# or-stm32-ds.net
KiCad netlist of a schematic drawn in EAGLE
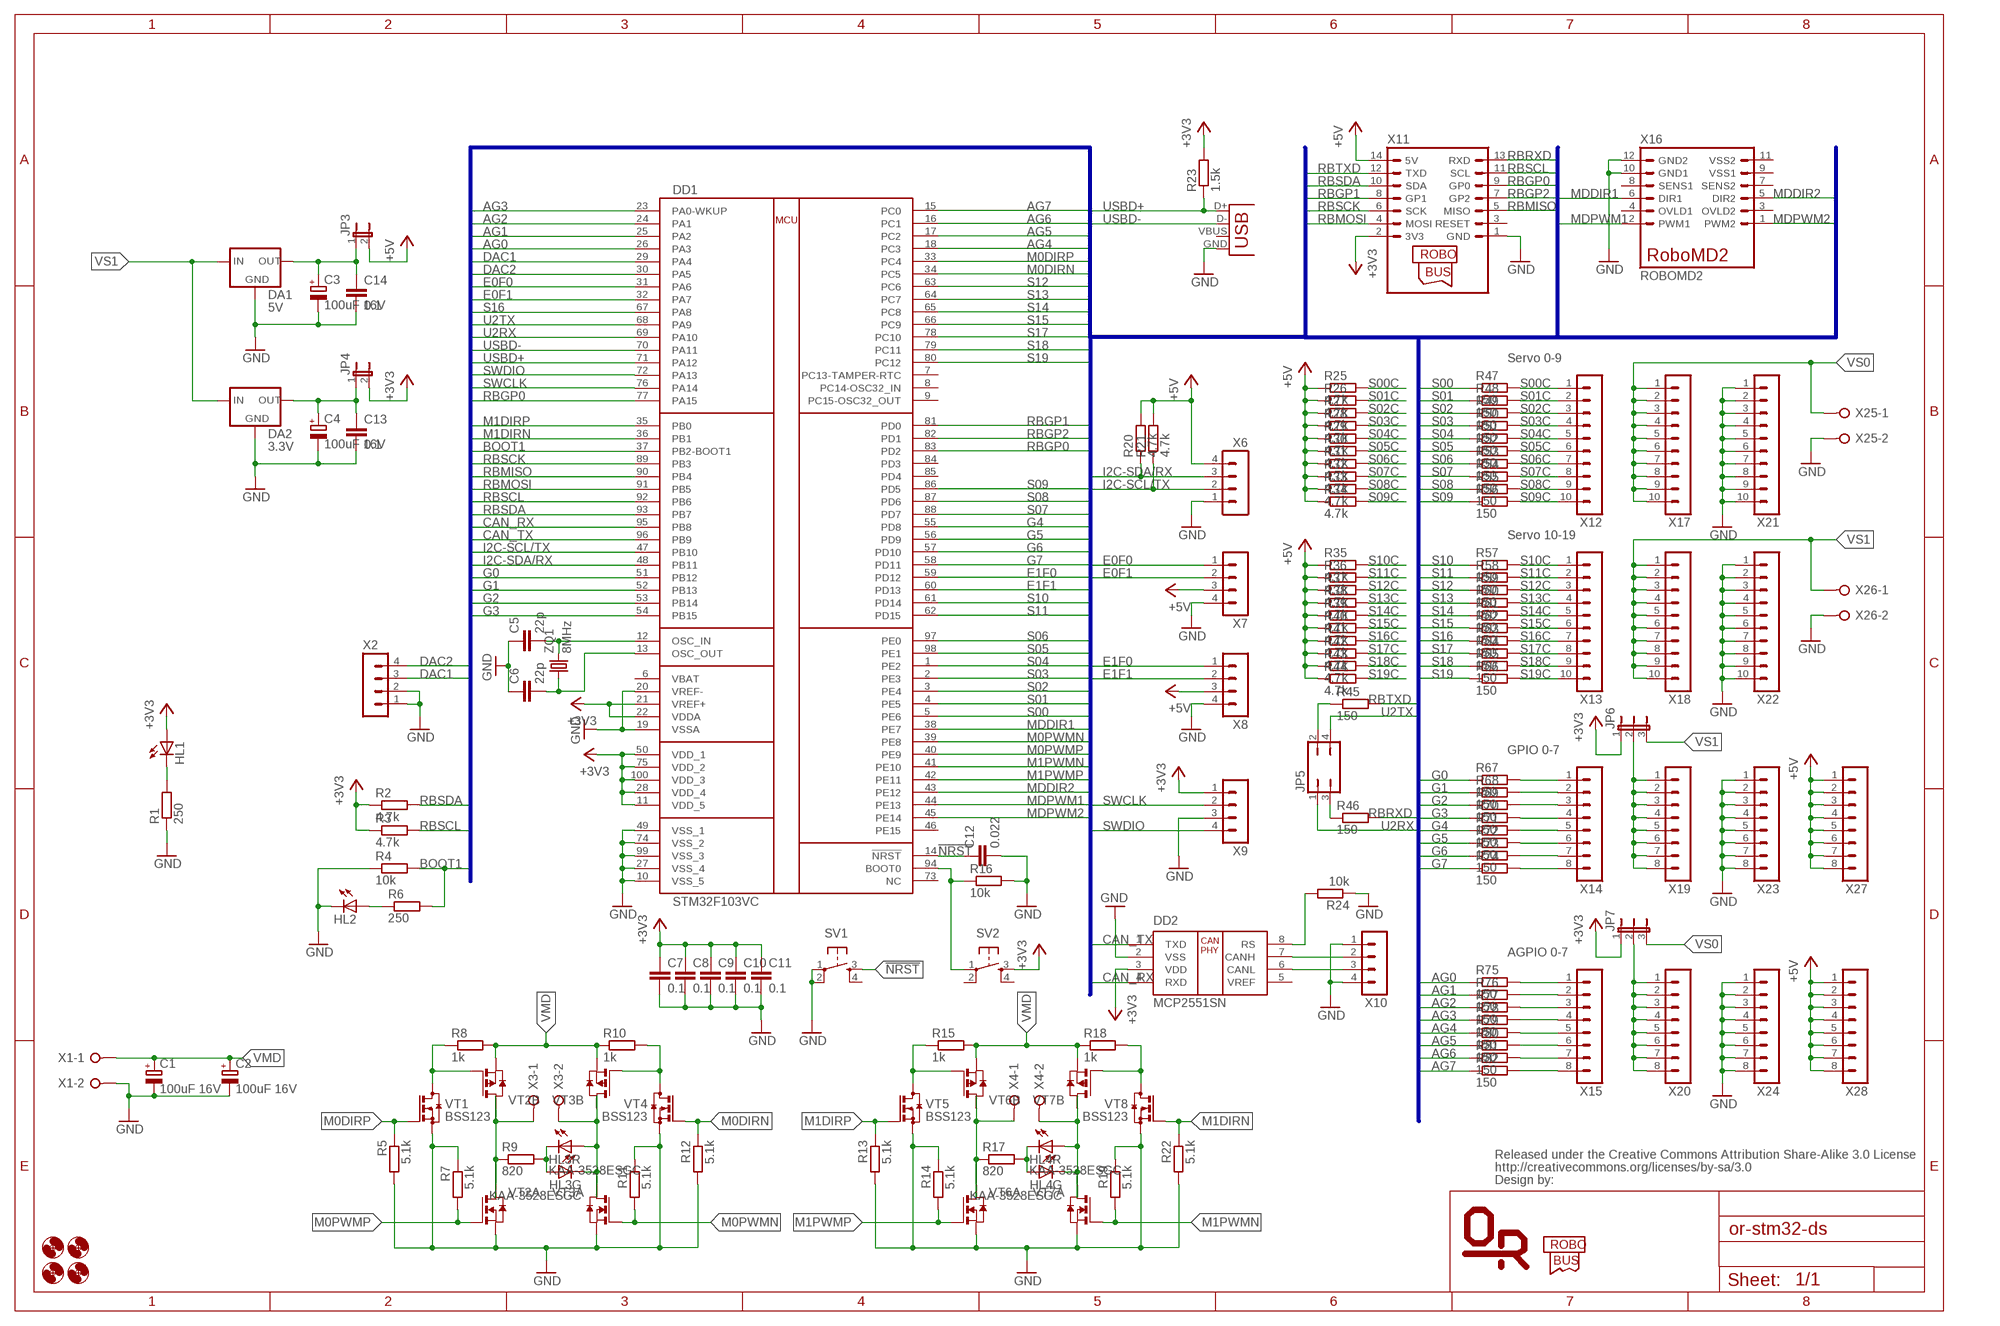
[diagram p0: schematic, sheet 1]

(export (version "E")
  (design (tool "Eeschema 10.0.6"))
  (components
    (comp (ref "C1")
      (value "100uF 16V")
      (footprint "eagle-import:E3,5-8")
      (libsource (lib "eagle-import") (part "CPOL-EUE3.5-8"))
    )
    (comp (ref "C2")
      (value "100uF 16V")
      (footprint "eagle-import:E3,5-8")
      (libsource (lib "eagle-import") (part "CPOL-EUE3.5-8"))
    )
    (comp (ref "C3")
      (value "100uF 16V")
      (footprint "eagle-import:E3,5-8")
      (libsource (lib "eagle-import") (part "CPOL-EUE3.5-8"))
    )
    (comp (ref "C4")
      (value "100uF 16V")
      (footprint "eagle-import:E3,5-8")
      (libsource (lib "eagle-import") (part "CPOL-EUE3.5-8"))
    )
    (comp (ref "C5")
      (value "22p")
      (footprint "eagle-import:C0603")
      (libsource (lib "eagle-import") (part "C-EUC0603"))
    )
    (comp (ref "C6")
      (value "22p")
      (footprint "eagle-import:C0603")
      (libsource (lib "eagle-import") (part "C-EUC0603"))
    )
    (comp (ref "C7")
      (value "0.1")
      (footprint "eagle-import:C0603")
      (libsource (lib "eagle-import") (part "C-EUC0603"))
    )
    (comp (ref "C8")
      (value "0.1")
      (footprint "eagle-import:C0603")
      (libsource (lib "eagle-import") (part "C-EUC0603"))
    )
    (comp (ref "C9")
      (value "0.1")
      (footprint "eagle-import:C0603")
      (libsource (lib "eagle-import") (part "C-EUC0603"))
    )
    (comp (ref "C10")
      (value "0.1")
      (footprint "eagle-import:C0603")
      (libsource (lib "eagle-import") (part "C-EUC0603"))
    )
    (comp (ref "C11")
      (value "0.1")
      (footprint "eagle-import:C0603")
      (libsource (lib "eagle-import") (part "C-EUC0603"))
    )
    (comp (ref "C12")
      (value "0.022")
      (footprint "eagle-import:C0603")
      (libsource (lib "eagle-import") (part "C-EUC0603"))
    )
    (comp (ref "C13")
      (value "0.1")
      (footprint "eagle-import:C0603")
      (libsource (lib "eagle-import") (part "C-EUC0603"))
    )
    (comp (ref "C14")
      (value "0.1")
      (footprint "eagle-import:C0603")
      (libsource (lib "eagle-import") (part "C-EUC0603"))
    )
    (comp (ref "DA1")
      (value "5V")
      (footprint "eagle-import:SOT223")
      (libsource (lib "eagle-import") (part "LM1117"))
    )
    (comp (ref "DA2")
      (value "3.3V")
      (footprint "eagle-import:SOT223")
      (libsource (lib "eagle-import") (part "LM1117"))
    )
    (comp (ref "DD1")
      (value "STM32F103VC")
      (footprint "eagle-import:LQFP100")
      (libsource (lib "eagle-import") (part "STM32F103VC"))
    )
    (comp (ref "DD2")
      (value "MCP2551SN")
      (footprint "eagle-import:SO-08")
      (libsource (lib "eagle-import") (part "MCP2551SN"))
    )
    (comp (ref "H1")
      (value "MOUNT-HOLE3.2")
      (footprint "eagle-import:3,2")
      (libsource (lib "eagle-import") (part "MOUNT-HOLE3.2"))
    )
    (comp (ref "H2")
      (value "MOUNT-HOLE3.2")
      (footprint "eagle-import:3,2")
      (libsource (lib "eagle-import") (part "MOUNT-HOLE3.2"))
    )
    (comp (ref "H3")
      (value "MOUNT-HOLE3.2")
      (footprint "eagle-import:3,2")
      (libsource (lib "eagle-import") (part "MOUNT-HOLE3.2"))
    )
    (comp (ref "H4")
      (value "MOUNT-HOLE3.2")
      (footprint "eagle-import:3,2")
      (libsource (lib "eagle-import") (part "MOUNT-HOLE3.2"))
    )
    (comp (ref "HL1")
      (value "LEDCHIP-LED0805")
      (footprint "eagle-import:CHIP-LED0805")
      (libsource (lib "eagle-import") (part "LEDCHIP-LED0805"))
    )
    (comp (ref "HL2")
      (value "LEDCHIP-LED0805")
      (footprint "eagle-import:CHIP-LED0805")
      (libsource (lib "eagle-import") (part "LEDCHIP-LED0805"))
    )
    (comp (ref "HL3")
      (value "KAA-3528ESGC")
      (footprint "eagle-import:KA-3528")
      (libsource (lib "eagle-import") (part "KAA-3528ESGC"))
    )
    (comp (ref "HL4")
      (value "KAA-3528ESGC")
      (footprint "eagle-import:KA-3528")
      (libsource (lib "eagle-import") (part "KAA-3528ESGC"))
    )
    (comp (ref "JP3")
      (value "JP1E")
      (footprint "eagle-import:JP1")
      (libsource (lib "eagle-import") (part "JP1E"))
    )
    (comp (ref "JP4")
      (value "JP1E")
      (footprint "eagle-import:JP1")
      (libsource (lib "eagle-import") (part "JP1E"))
    )
    (comp (ref "JP5")
      (value "JP2Q")
      (footprint "eagle-import:JP2Q")
      (libsource (lib "eagle-import") (part "JP2Q"))
    )
    (comp (ref "JP6")
      (value "JP2E")
      (footprint "eagle-import:JP2")
      (libsource (lib "eagle-import") (part "JP2E"))
    )
    (comp (ref "JP7")
      (value "JP2E")
      (footprint "eagle-import:JP2")
      (libsource (lib "eagle-import") (part "JP2E"))
    )
    (comp (ref "R1")
      (value "250")
      (footprint "eagle-import:R0603")
      (libsource (lib "eagle-import") (part "R-EU_R0603"))
    )
    (comp (ref "R2")
      (value "4.7k")
      (footprint "eagle-import:R0603")
      (libsource (lib "eagle-import") (part "R-EU_R0603"))
    )
    (comp (ref "R3")
      (value "4.7k")
      (footprint "eagle-import:R0603")
      (libsource (lib "eagle-import") (part "R-EU_R0603"))
    )
    (comp (ref "R4")
      (value "10k")
      (footprint "eagle-import:R0603")
      (libsource (lib "eagle-import") (part "R-EU_R0603"))
    )
    (comp (ref "R5")
      (value "5.1k")
      (footprint "eagle-import:R0603")
      (libsource (lib "eagle-import") (part "R-EU_R0603"))
    )
    (comp (ref "R6")
      (value "250")
      (footprint "eagle-import:R0603")
      (libsource (lib "eagle-import") (part "R-EU_R0603"))
    )
    (comp (ref "R7")
      (value "5.1k")
      (footprint "eagle-import:R0603")
      (libsource (lib "eagle-import") (part "R-EU_R0603"))
    )
    (comp (ref "R8")
      (value "1k")
      (footprint "eagle-import:R0603")
      (libsource (lib "eagle-import") (part "R-EU_R0603"))
    )
    (comp (ref "R9")
      (value "820")
      (footprint "eagle-import:R0603")
      (libsource (lib "eagle-import") (part "R-EU_R0603"))
    )
    (comp (ref "R10")
      (value "1k")
      (footprint "eagle-import:R0603")
      (libsource (lib "eagle-import") (part "R-EU_R0603"))
    )
    (comp (ref "R11")
      (value "5.1k")
      (footprint "eagle-import:R0603")
      (libsource (lib "eagle-import") (part "R-EU_R0603"))
    )
    (comp (ref "R12")
      (value "5.1k")
      (footprint "eagle-import:R0603")
      (libsource (lib "eagle-import") (part "R-EU_R0603"))
    )
    (comp (ref "R13")
      (value "5.1k")
      (footprint "eagle-import:R0603")
      (libsource (lib "eagle-import") (part "R-EU_R0603"))
    )
    (comp (ref "R14")
      (value "5.1k")
      (footprint "eagle-import:R0603")
      (libsource (lib "eagle-import") (part "R-EU_R0603"))
    )
    (comp (ref "R15")
      (value "1k")
      (footprint "eagle-import:R0603")
      (libsource (lib "eagle-import") (part "R-EU_R0603"))
    )
    (comp (ref "R16")
      (value "10k")
      (footprint "eagle-import:R0603")
      (libsource (lib "eagle-import") (part "R-EU_R0603"))
    )
    (comp (ref "R17")
      (value "820")
      (footprint "eagle-import:R0603")
      (libsource (lib "eagle-import") (part "R-EU_R0603"))
    )
    (comp (ref "R18")
      (value "1k")
      (footprint "eagle-import:R0603")
      (libsource (lib "eagle-import") (part "R-EU_R0603"))
    )
    (comp (ref "R19")
      (value "5.1k")
      (footprint "eagle-import:R0603")
      (libsource (lib "eagle-import") (part "R-EU_R0603"))
    )
    (comp (ref "R20")
      (value "4.7k")
      (footprint "eagle-import:R0603")
      (libsource (lib "eagle-import") (part "R-EU_R0603"))
    )
    (comp (ref "R21")
      (value "4.7k")
      (footprint "eagle-import:R0603")
      (libsource (lib "eagle-import") (part "R-EU_R0603"))
    )
    (comp (ref "R22")
      (value "5.1k")
      (footprint "eagle-import:R0603")
      (libsource (lib "eagle-import") (part "R-EU_R0603"))
    )
    (comp (ref "R23")
      (value "1.5k")
      (footprint "eagle-import:R0603")
      (libsource (lib "eagle-import") (part "R-EU_R0603"))
    )
    (comp (ref "R24")
      (value "10k")
      (footprint "eagle-import:R0603")
      (libsource (lib "eagle-import") (part "R-EU_R0603"))
    )
    (comp (ref "R25")
      (value "4.7k")
      (footprint "eagle-import:R0603")
      (libsource (lib "eagle-import") (part "R-EU_R0603"))
    )
    (comp (ref "R26")
      (value "4.7k")
      (footprint "eagle-import:R0603")
      (libsource (lib "eagle-import") (part "R-EU_R0603"))
    )
    (comp (ref "R27")
      (value "4.7k")
      (footprint "eagle-import:R0603")
      (libsource (lib "eagle-import") (part "R-EU_R0603"))
    )
    (comp (ref "R28")
      (value "4.7k")
      (footprint "eagle-import:R0603")
      (libsource (lib "eagle-import") (part "R-EU_R0603"))
    )
    (comp (ref "R29")
      (value "4.7k")
      (footprint "eagle-import:R0603")
      (libsource (lib "eagle-import") (part "R-EU_R0603"))
    )
    (comp (ref "R30")
      (value "4.7k")
      (footprint "eagle-import:R0603")
      (libsource (lib "eagle-import") (part "R-EU_R0603"))
    )
    (comp (ref "R31")
      (value "4.7k")
      (footprint "eagle-import:R0603")
      (libsource (lib "eagle-import") (part "R-EU_R0603"))
    )
    (comp (ref "R32")
      (value "4.7k")
      (footprint "eagle-import:R0603")
      (libsource (lib "eagle-import") (part "R-EU_R0603"))
    )
    (comp (ref "R33")
      (value "4.7k")
      (footprint "eagle-import:R0603")
      (libsource (lib "eagle-import") (part "R-EU_R0603"))
    )
    (comp (ref "R34")
      (value "4.7k")
      (footprint "eagle-import:R0603")
      (libsource (lib "eagle-import") (part "R-EU_R0603"))
    )
    (comp (ref "R35")
      (value "4.7k")
      (footprint "eagle-import:R0603")
      (libsource (lib "eagle-import") (part "R-EU_R0603"))
    )
    (comp (ref "R36")
      (value "4.7k")
      (footprint "eagle-import:R0603")
      (libsource (lib "eagle-import") (part "R-EU_R0603"))
    )
    (comp (ref "R37")
      (value "4.7k")
      (footprint "eagle-import:R0603")
      (libsource (lib "eagle-import") (part "R-EU_R0603"))
    )
    (comp (ref "R38")
      (value "4.7k")
      (footprint "eagle-import:R0603")
      (libsource (lib "eagle-import") (part "R-EU_R0603"))
    )
    (comp (ref "R39")
      (value "4.7k")
      (footprint "eagle-import:R0603")
      (libsource (lib "eagle-import") (part "R-EU_R0603"))
    )
    (comp (ref "R40")
      (value "4.7k")
      (footprint "eagle-import:R0603")
      (libsource (lib "eagle-import") (part "R-EU_R0603"))
    )
    (comp (ref "R41")
      (value "4.7k")
      (footprint "eagle-import:R0603")
      (libsource (lib "eagle-import") (part "R-EU_R0603"))
    )
    (comp (ref "R42")
      (value "4.7k")
      (footprint "eagle-import:R0603")
      (libsource (lib "eagle-import") (part "R-EU_R0603"))
    )
    (comp (ref "R43")
      (value "4.7k")
      (footprint "eagle-import:R0603")
      (libsource (lib "eagle-import") (part "R-EU_R0603"))
    )
    (comp (ref "R44")
      (value "4.7k")
      (footprint "eagle-import:R0603")
      (libsource (lib "eagle-import") (part "R-EU_R0603"))
    )
    (comp (ref "R45")
      (value "150")
      (footprint "eagle-import:R0603")
      (libsource (lib "eagle-import") (part "R-EU_R0603"))
    )
    (comp (ref "R46")
      (value "150")
      (footprint "eagle-import:R0603")
      (libsource (lib "eagle-import") (part "R-EU_R0603"))
    )
    (comp (ref "R47")
      (value "150")
      (footprint "eagle-import:R0603")
      (libsource (lib "eagle-import") (part "R-EU_R0603"))
    )
    (comp (ref "R48")
      (value "150")
      (footprint "eagle-import:R0603")
      (libsource (lib "eagle-import") (part "R-EU_R0603"))
    )
    (comp (ref "R49")
      (value "150")
      (footprint "eagle-import:R0603")
      (libsource (lib "eagle-import") (part "R-EU_R0603"))
    )
    (comp (ref "R50")
      (value "150")
      (footprint "eagle-import:R0603")
      (libsource (lib "eagle-import") (part "R-EU_R0603"))
    )
    (comp (ref "R51")
      (value "150")
      (footprint "eagle-import:R0603")
      (libsource (lib "eagle-import") (part "R-EU_R0603"))
    )
    (comp (ref "R52")
      (value "150")
      (footprint "eagle-import:R0603")
      (libsource (lib "eagle-import") (part "R-EU_R0603"))
    )
    (comp (ref "R53")
      (value "150")
      (footprint "eagle-import:R0603")
      (libsource (lib "eagle-import") (part "R-EU_R0603"))
    )
    (comp (ref "R54")
      (value "150")
      (footprint "eagle-import:R0603")
      (libsource (lib "eagle-import") (part "R-EU_R0603"))
    )
    (comp (ref "R55")
      (value "150")
      (footprint "eagle-import:R0603")
      (libsource (lib "eagle-import") (part "R-EU_R0603"))
    )
    (comp (ref "R56")
      (value "150")
      (footprint "eagle-import:R0603")
      (libsource (lib "eagle-import") (part "R-EU_R0603"))
    )
    (comp (ref "R57")
      (value "150")
      (footprint "eagle-import:R0603")
      (libsource (lib "eagle-import") (part "R-EU_R0603"))
    )
    (comp (ref "R58")
      (value "150")
      (footprint "eagle-import:R0603")
      (libsource (lib "eagle-import") (part "R-EU_R0603"))
    )
    (comp (ref "R59")
      (value "150")
      (footprint "eagle-import:R0603")
      (libsource (lib "eagle-import") (part "R-EU_R0603"))
    )
    (comp (ref "R60")
      (value "150")
      (footprint "eagle-import:R0603")
      (libsource (lib "eagle-import") (part "R-EU_R0603"))
    )
    (comp (ref "R61")
      (value "150")
      (footprint "eagle-import:R0603")
      (libsource (lib "eagle-import") (part "R-EU_R0603"))
    )
    (comp (ref "R62")
      (value "150")
      (footprint "eagle-import:R0603")
      (libsource (lib "eagle-import") (part "R-EU_R0603"))
    )
    (comp (ref "R63")
      (value "150")
      (footprint "eagle-import:R0603")
      (libsource (lib "eagle-import") (part "R-EU_R0603"))
    )
    (comp (ref "R64")
      (value "150")
      (footprint "eagle-import:R0603")
      (libsource (lib "eagle-import") (part "R-EU_R0603"))
    )
    (comp (ref "R65")
      (value "150")
      (footprint "eagle-import:R0603")
      (libsource (lib "eagle-import") (part "R-EU_R0603"))
    )
    (comp (ref "R66")
      (value "150")
      (footprint "eagle-import:R0603")
      (libsource (lib "eagle-import") (part "R-EU_R0603"))
    )
    (comp (ref "R67")
      (value "150")
      (footprint "eagle-import:R0603")
      (libsource (lib "eagle-import") (part "R-EU_R0603"))
    )
    (comp (ref "R68")
      (value "150")
      (footprint "eagle-import:R0603")
      (libsource (lib "eagle-import") (part "R-EU_R0603"))
    )
    (comp (ref "R69")
      (value "150")
      (footprint "eagle-import:R0603")
      (libsource (lib "eagle-import") (part "R-EU_R0603"))
    )
    (comp (ref "R70")
      (value "150")
      (footprint "eagle-import:R0603")
      (libsource (lib "eagle-import") (part "R-EU_R0603"))
    )
    (comp (ref "R71")
      (value "150")
      (footprint "eagle-import:R0603")
      (libsource (lib "eagle-import") (part "R-EU_R0603"))
    )
    (comp (ref "R72")
      (value "150")
      (footprint "eagle-import:R0603")
      (libsource (lib "eagle-import") (part "R-EU_R0603"))
    )
    (comp (ref "R73")
      (value "150")
      (footprint "eagle-import:R0603")
      (libsource (lib "eagle-import") (part "R-EU_R0603"))
    )
    (comp (ref "R74")
      (value "150")
      (footprint "eagle-import:R0603")
      (libsource (lib "eagle-import") (part "R-EU_R0603"))
    )
    (comp (ref "R75")
      (value "150")
      (footprint "eagle-import:R0603")
      (libsource (lib "eagle-import") (part "R-EU_R0603"))
    )
    (comp (ref "R76")
      (value "150")
      (footprint "eagle-import:R0603")
      (libsource (lib "eagle-import") (part "R-EU_R0603"))
    )
    (comp (ref "R77")
      (value "150")
      (footprint "eagle-import:R0603")
      (libsource (lib "eagle-import") (part "R-EU_R0603"))
    )
    (comp (ref "R78")
      (value "150")
      (footprint "eagle-import:R0603")
      (libsource (lib "eagle-import") (part "R-EU_R0603"))
    )
    (comp (ref "R79")
      (value "150")
      (footprint "eagle-import:R0603")
      (libsource (lib "eagle-import") (part "R-EU_R0603"))
    )
    (comp (ref "R80")
      (value "150")
      (footprint "eagle-import:R0603")
      (libsource (lib "eagle-import") (part "R-EU_R0603"))
    )
    (comp (ref "R81")
      (value "150")
      (footprint "eagle-import:R0603")
      (libsource (lib "eagle-import") (part "R-EU_R0603"))
    )
    (comp (ref "R82")
      (value "150")
      (footprint "eagle-import:R0603")
      (libsource (lib "eagle-import") (part "R-EU_R0603"))
    )
    (comp (ref "SV1")
      (value "TAC_SWITCHSMD")
      (footprint "eagle-import:TACTILE_SWITCH_SMD")
      (libsource (lib "eagle-import") (part "TAC_SWITCHSMD"))
    )
    (comp (ref "SV2")
      (value "TAC_SWITCHSMD")
      (footprint "eagle-import:TACTILE_SWITCH_SMD")
      (libsource (lib "eagle-import") (part "TAC_SWITCHSMD"))
    )
    (comp (ref "U$1")
      (value "CREATIVE_COMMONS_BY-SA")
      (footprint "eagle-import:CC-BY-SA-6MM")
      (fields (field (name "AUTHOR") "Open Robotics Team"))
      (libsource (lib "eagle-import") (part "CREATIVE_COMMONS_BY-SA"))
    )
    (comp (ref "U$2")
      (value "ORLOGO")
      (footprint "eagle-import:ORLOGO")
      (libsource (lib "eagle-import") (part "ORLOGO"))
    )
    (comp (ref "U$3")
      (value "ROBOBUS_LOGO")
      (footprint "eagle-import:ROBOBUS_LOGO")
      (libsource (lib "eagle-import") (part "ROBOBUS_LOGO"))
    )
    (comp (ref "VT1")
      (value "BSS123")
      (footprint "eagle-import:SOT23")
      (libsource (lib "eagle-import") (part "BSS123"))
    )
    (comp (ref "VT2")
      (value "PN_MOSFET-SO8")
      (footprint "eagle-import:SO8")
      (libsource (lib "eagle-import") (part "PN_MOSFET-SO8"))
    )
    (comp (ref "VT3")
      (value "PN_MOSFET-SO8")
      (footprint "eagle-import:SO8")
      (libsource (lib "eagle-import") (part "PN_MOSFET-SO8"))
    )
    (comp (ref "VT4")
      (value "BSS123")
      (footprint "eagle-import:SOT23")
      (libsource (lib "eagle-import") (part "BSS123"))
    )
    (comp (ref "VT5")
      (value "BSS123")
      (footprint "eagle-import:SOT23")
      (libsource (lib "eagle-import") (part "BSS123"))
    )
    (comp (ref "VT6")
      (value "PN_MOSFET-SO8")
      (footprint "eagle-import:SO8")
      (libsource (lib "eagle-import") (part "PN_MOSFET-SO8"))
    )
    (comp (ref "VT7")
      (value "PN_MOSFET-SO8")
      (footprint "eagle-import:SO8")
      (libsource (lib "eagle-import") (part "PN_MOSFET-SO8"))
    )
    (comp (ref "VT8")
      (value "BSS123")
      (footprint "eagle-import:SOT23")
      (libsource (lib "eagle-import") (part "BSS123"))
    )
    (comp (ref "X1")
      (value "HT396R-02P")
      (footprint "eagle-import:HT396R-02P")
      (libsource (lib "eagle-import") (part "HT396R-02P"))
    )
    (comp (ref "X2")
      (value "MA04-11.27MM")
      (footprint "eagle-import:1X04-1.27MM")
      (libsource (lib "eagle-import") (part "MA04-11.27MM"))
    )
    (comp (ref "X3")
      (value "HT396R-02P")
      (footprint "eagle-import:HT396R-02P")
      (libsource (lib "eagle-import") (part "HT396R-02P"))
    )
    (comp (ref "X4")
      (value "HT396R-02P")
      (footprint "eagle-import:HT396R-02P")
      (libsource (lib "eagle-import") (part "HT396R-02P"))
    )
    (comp (ref "X5")
      (value "USBSMD")
      (footprint "eagle-import:USB-MINIB")
      (libsource (lib "eagle-import") (part "USBSMD"))
    )
    (comp (ref "X6")
      (value "MA04-1")
      (footprint "eagle-import:MA04-1")
      (libsource (lib "eagle-import") (part "MA04-1"))
    )
    (comp (ref "X7")
      (value "MA04-1")
      (footprint "eagle-import:MA04-1")
      (libsource (lib "eagle-import") (part "MA04-1"))
    )
    (comp (ref "X8")
      (value "MA04-1")
      (footprint "eagle-import:MA04-1")
      (libsource (lib "eagle-import") (part "MA04-1"))
    )
    (comp (ref "X9")
      (value "MA04-11.27MM")
      (footprint "eagle-import:1X04-1.27MM")
      (libsource (lib "eagle-import") (part "MA04-11.27MM"))
    )
    (comp (ref "X10")
      (value "MA04-1")
      (footprint "eagle-import:MA04-1")
      (libsource (lib "eagle-import") (part "MA04-1"))
    )
    (comp (ref "X11")
      (value "ROBOBUSR")
      (footprint "eagle-import:ML14L")
      (libsource (lib "eagle-import") (part "ROBOBUSR"))
    )
    (comp (ref "X12")
      (value "MA10-1")
      (footprint "eagle-import:MA10-1")
      (libsource (lib "eagle-import") (part "MA10-1"))
    )
    (comp (ref "X13")
      (value "MA10-1")
      (footprint "eagle-import:MA10-1")
      (libsource (lib "eagle-import") (part "MA10-1"))
    )
    (comp (ref "X14")
      (value "MA08-1")
      (footprint "eagle-import:MA08-1")
      (libsource (lib "eagle-import") (part "MA08-1"))
    )
    (comp (ref "X15")
      (value "MA08-1")
      (footprint "eagle-import:MA08-1")
      (libsource (lib "eagle-import") (part "MA08-1"))
    )
    (comp (ref "X16")
      (value "ROBOMD2")
      (footprint "eagle-import:ML12")
      (libsource (lib "eagle-import") (part "ROBOMD2"))
    )
    (comp (ref "X17")
      (value "MA10-1")
      (footprint "eagle-import:MA10-1")
      (libsource (lib "eagle-import") (part "MA10-1"))
    )
    (comp (ref "X18")
      (value "MA10-1")
      (footprint "eagle-import:MA10-1")
      (libsource (lib "eagle-import") (part "MA10-1"))
    )
    (comp (ref "X19")
      (value "MA08-1")
      (footprint "eagle-import:MA08-1")
      (libsource (lib "eagle-import") (part "MA08-1"))
    )
    (comp (ref "X20")
      (value "MA08-1")
      (footprint "eagle-import:MA08-1")
      (libsource (lib "eagle-import") (part "MA08-1"))
    )
    (comp (ref "X21")
      (value "MA10-1")
      (footprint "eagle-import:MA10-1")
      (libsource (lib "eagle-import") (part "MA10-1"))
    )
    (comp (ref "X22")
      (value "MA10-1")
      (footprint "eagle-import:MA10-1")
      (libsource (lib "eagle-import") (part "MA10-1"))
    )
    (comp (ref "X23")
      (value "MA08-1")
      (footprint "eagle-import:MA08-1")
      (libsource (lib "eagle-import") (part "MA08-1"))
    )
    (comp (ref "X24")
      (value "MA08-1")
      (footprint "eagle-import:MA08-1")
      (libsource (lib "eagle-import") (part "MA08-1"))
    )
    (comp (ref "X25")
      (value "W237-02P")
      (footprint "eagle-import:W237-132")
      (libsource (lib "eagle-import") (part "W237-02P"))
    )
    (comp (ref "X26")
      (value "W237-02P")
      (footprint "eagle-import:W237-132")
      (libsource (lib "eagle-import") (part "W237-02P"))
    )
    (comp (ref "X27")
      (value "MA08-1")
      (footprint "eagle-import:MA08-1")
      (libsource (lib "eagle-import") (part "MA08-1"))
    )
    (comp (ref "X28")
      (value "MA08-1")
      (footprint "eagle-import:MA08-1")
      (libsource (lib "eagle-import") (part "MA08-1"))
    )
    (comp (ref "ZQ1")
      (value "8MHz")
      (footprint "eagle-import:HC49U-V")
      (libsource (lib "eagle-import") (part "CRYSTALHC49U-V"))
    )
  )
  (nets
    (net (code "1") (name "+3V3") (class "Default")
      (node (ref "C10") (pin "1") (pinfunction "1_1") (pintype "passive"))
      (node (ref "C11") (pin "1") (pinfunction "1_1") (pintype "passive"))
      (node (ref "C7") (pin "1") (pinfunction "1_1") (pintype "passive"))
      (node (ref "C8") (pin "1") (pinfunction "1_1") (pintype "passive"))
      (node (ref "C9") (pin "1") (pinfunction "1_1") (pintype "passive"))
      (node (ref "DD1") (pin "100") (pinfunction "VDD_3_100") (pintype "power_in"))
      (node (ref "DD1") (pin "11") (pinfunction "VDD_5_11") (pintype "power_in"))
      (node (ref "DD1") (pin "21") (pinfunction "VREF+_21") (pintype "bidirectional"))
      (node (ref "DD1") (pin "22") (pinfunction "VDDA_22") (pintype "bidirectional"))
      (node (ref "DD1") (pin "28") (pinfunction "VDD_4_28") (pintype "power_in"))
      (node (ref "DD1") (pin "50") (pinfunction "VDD_1_50") (pintype "power_in"))
      (node (ref "DD1") (pin "75") (pinfunction "VDD_2_75") (pintype "power_in"))
      (node (ref "DD2") (pin "3") (pinfunction "VDD_3") (pintype "power_in"))
      (node (ref "HL1") (pin "A") (pinfunction "A_A") (pintype "passive"))
      (node (ref "JP4") (pin "2") (pinfunction "2_2") (pintype "passive"))
      (node (ref "JP6") (pin "1") (pinfunction "1_1") (pintype "passive"))
      (node (ref "JP7") (pin "1") (pinfunction "1_1") (pintype "passive"))
      (node (ref "R2") (pin "1") (pinfunction "1_1") (pintype "passive"))
      (node (ref "R23") (pin "2") (pinfunction "2_2") (pintype "passive"))
      (node (ref "R3") (pin "1") (pinfunction "1_1") (pintype "passive"))
      (node (ref "SV2") (pin "3") (pinfunction "3_3") (pintype "passive"))
      (node (ref "X11") (pin "2") (pinfunction "3V3_2") (pintype "passive"))
      (node (ref "X9") (pin "1") (pinfunction "1_1") (pintype "passive"))
    )
    (net (code "2") (name "+5V") (class "Default")
      (node (ref "JP3") (pin "2") (pinfunction "2_2") (pintype "passive"))
      (node (ref "R20") (pin "2") (pinfunction "2_2") (pintype "passive"))
      (node (ref "R21") (pin "2") (pinfunction "2_2") (pintype "passive"))
      (node (ref "R25") (pin "1") (pinfunction "1_1") (pintype "passive"))
      (node (ref "R26") (pin "1") (pinfunction "1_1") (pintype "passive"))
      (node (ref "R27") (pin "1") (pinfunction "1_1") (pintype "passive"))
      (node (ref "R28") (pin "1") (pinfunction "1_1") (pintype "passive"))
      (node (ref "R29") (pin "1") (pinfunction "1_1") (pintype "passive"))
      (node (ref "R30") (pin "1") (pinfunction "1_1") (pintype "passive"))
      (node (ref "R31") (pin "1") (pinfunction "1_1") (pintype "passive"))
      (node (ref "R32") (pin "1") (pinfunction "1_1") (pintype "passive"))
      (node (ref "R33") (pin "1") (pinfunction "1_1") (pintype "passive"))
      (node (ref "R34") (pin "1") (pinfunction "1_1") (pintype "passive"))
      (node (ref "R35") (pin "1") (pinfunction "1_1") (pintype "passive"))
      (node (ref "R36") (pin "1") (pinfunction "1_1") (pintype "passive"))
      (node (ref "R37") (pin "1") (pinfunction "1_1") (pintype "passive"))
      (node (ref "R38") (pin "1") (pinfunction "1_1") (pintype "passive"))
      (node (ref "R39") (pin "1") (pinfunction "1_1") (pintype "passive"))
      (node (ref "R40") (pin "1") (pinfunction "1_1") (pintype "passive"))
      (node (ref "R41") (pin "1") (pinfunction "1_1") (pintype "passive"))
      (node (ref "R42") (pin "1") (pinfunction "1_1") (pintype "passive"))
      (node (ref "R43") (pin "1") (pinfunction "1_1") (pintype "passive"))
      (node (ref "R44") (pin "1") (pinfunction "1_1") (pintype "passive"))
      (node (ref "X11") (pin "14") (pinfunction "5V_14") (pintype "passive"))
      (node (ref "X27") (pin "1") (pinfunction "1_1") (pintype "passive"))
      (node (ref "X27") (pin "2") (pinfunction "2_2") (pintype "passive"))
      (node (ref "X27") (pin "3") (pinfunction "3_3") (pintype "passive"))
      (node (ref "X27") (pin "4") (pinfunction "4_4") (pintype "passive"))
      (node (ref "X27") (pin "5") (pinfunction "5_5") (pintype "passive"))
      (node (ref "X27") (pin "6") (pinfunction "6_6") (pintype "passive"))
      (node (ref "X27") (pin "7") (pinfunction "7_7") (pintype "passive"))
      (node (ref "X27") (pin "8") (pinfunction "8_8") (pintype "passive"))
      (node (ref "X28") (pin "1") (pinfunction "1_1") (pintype "passive"))
      (node (ref "X28") (pin "2") (pinfunction "2_2") (pintype "passive"))
      (node (ref "X28") (pin "3") (pinfunction "3_3") (pintype "passive"))
      (node (ref "X28") (pin "4") (pinfunction "4_4") (pintype "passive"))
      (node (ref "X28") (pin "5") (pinfunction "5_5") (pintype "passive"))
      (node (ref "X28") (pin "6") (pinfunction "6_6") (pintype "passive"))
      (node (ref "X28") (pin "7") (pinfunction "7_7") (pintype "passive"))
      (node (ref "X28") (pin "8") (pinfunction "8_8") (pintype "passive"))
      (node (ref "X6") (pin "4") (pinfunction "4_4") (pintype "passive"))
      (node (ref "X7") (pin "3") (pinfunction "3_3") (pintype "passive"))
      (node (ref "X8") (pin "3") (pinfunction "3_3") (pintype "passive"))
    )
    (net (code "3") (name "/AG0") (class "Default")
      (node (ref "DD1") (pin "26") (pinfunction "PA3_26") (pintype "bidirectional"))
      (node (ref "R75") (pin "1") (pinfunction "1_1") (pintype "passive"))
    )
    (net (code "4") (name "/AG1") (class "Default")
      (node (ref "DD1") (pin "25") (pinfunction "PA2_25") (pintype "bidirectional"))
      (node (ref "R76") (pin "1") (pinfunction "1_1") (pintype "passive"))
    )
    (net (code "5") (name "/AG2") (class "Default")
      (node (ref "DD1") (pin "24") (pinfunction "PA1_24") (pintype "bidirectional"))
      (node (ref "R77") (pin "1") (pinfunction "1_1") (pintype "passive"))
    )
    (net (code "6") (name "/AG3") (class "Default")
      (node (ref "DD1") (pin "23") (pinfunction "PA0-WKUP_23") (pintype "bidirectional"))
      (node (ref "R78") (pin "1") (pinfunction "1_1") (pintype "passive"))
    )
    (net (code "7") (name "/AG4") (class "Default")
      (node (ref "DD1") (pin "18") (pinfunction "PC3_18") (pintype "bidirectional"))
      (node (ref "R79") (pin "1") (pinfunction "1_1") (pintype "passive"))
    )
    (net (code "8") (name "/AG5") (class "Default")
      (node (ref "DD1") (pin "17") (pinfunction "PC2_17") (pintype "bidirectional"))
      (node (ref "R80") (pin "1") (pinfunction "1_1") (pintype "passive"))
    )
    (net (code "9") (name "/AG6") (class "Default")
      (node (ref "DD1") (pin "16") (pinfunction "PC1_16") (pintype "bidirectional"))
      (node (ref "R81") (pin "1") (pinfunction "1_1") (pintype "passive"))
    )
    (net (code "10") (name "/AG7") (class "Default")
      (node (ref "DD1") (pin "15") (pinfunction "PC0_15") (pintype "bidirectional"))
      (node (ref "R82") (pin "1") (pinfunction "1_1") (pintype "passive"))
    )
    (net (code "11") (name "/BOOT1") (class "Default")
      (node (ref "DD1") (pin "37") (pinfunction "PB2-BOOT1_37") (pintype "bidirectional"))
      (node (ref "R4") (pin "2") (pinfunction "2_2") (pintype "passive"))
      (node (ref "R6") (pin "2") (pinfunction "2_2") (pintype "passive"))
    )
    (net (code "12") (name "/CAN_RX") (class "Default")
      (node (ref "DD1") (pin "95") (pinfunction "PB8_95") (pintype "bidirectional"))
      (node (ref "DD2") (pin "4") (pinfunction "RXD_4") (pintype "output"))
    )
    (net (code "13") (name "/CAN_TX") (class "Default")
      (node (ref "DD1") (pin "96") (pinfunction "PB9_96") (pintype "bidirectional"))
      (node (ref "DD2") (pin "1") (pinfunction "TXD_1") (pintype "input"))
    )
    (net (code "14") (name "/DAC1") (class "Default")
      (node (ref "DD1") (pin "29") (pinfunction "PA4_29") (pintype "bidirectional"))
      (node (ref "X2") (pin "3") (pinfunction "3_3") (pintype "passive"))
    )
    (net (code "15") (name "/DAC2") (class "Default")
      (node (ref "DD1") (pin "30") (pinfunction "PA5_30") (pintype "bidirectional"))
      (node (ref "X2") (pin "4") (pinfunction "4_4") (pintype "passive"))
    )
    (net (code "16") (name "/E0F0") (class "Default")
      (node (ref "DD1") (pin "31") (pinfunction "PA6_31") (pintype "bidirectional"))
      (node (ref "X7") (pin "1") (pinfunction "1_1") (pintype "passive"))
    )
    (net (code "17") (name "/E0F1") (class "Default")
      (node (ref "DD1") (pin "32") (pinfunction "PA7_32") (pintype "bidirectional"))
      (node (ref "X7") (pin "2") (pinfunction "2_2") (pintype "passive"))
    )
    (net (code "18") (name "/E1F0") (class "Default")
      (node (ref "DD1") (pin "59") (pinfunction "PD12_59") (pintype "bidirectional"))
      (node (ref "X8") (pin "1") (pinfunction "1_1") (pintype "passive"))
    )
    (net (code "19") (name "/E1F1") (class "Default")
      (node (ref "DD1") (pin "60") (pinfunction "PD13_60") (pintype "bidirectional"))
      (node (ref "X8") (pin "2") (pinfunction "2_2") (pintype "passive"))
    )
    (net (code "20") (name "/G0") (class "Default")
      (node (ref "DD1") (pin "51") (pinfunction "PB12_51") (pintype "bidirectional"))
      (node (ref "R67") (pin "1") (pinfunction "1_1") (pintype "passive"))
    )
    (net (code "21") (name "/G1") (class "Default")
      (node (ref "DD1") (pin "52") (pinfunction "PB13_52") (pintype "bidirectional"))
      (node (ref "R68") (pin "1") (pinfunction "1_1") (pintype "passive"))
    )
    (net (code "22") (name "/G2") (class "Default")
      (node (ref "DD1") (pin "53") (pinfunction "PB14_53") (pintype "bidirectional"))
      (node (ref "R69") (pin "1") (pinfunction "1_1") (pintype "passive"))
    )
    (net (code "23") (name "/G3") (class "Default")
      (node (ref "DD1") (pin "54") (pinfunction "PB15_54") (pintype "bidirectional"))
      (node (ref "R70") (pin "1") (pinfunction "1_1") (pintype "passive"))
    )
    (net (code "24") (name "/G4") (class "Default")
      (node (ref "DD1") (pin "55") (pinfunction "PD8_55") (pintype "bidirectional"))
      (node (ref "R71") (pin "1") (pinfunction "1_1") (pintype "passive"))
    )
    (net (code "25") (name "/G5") (class "Default")
      (node (ref "DD1") (pin "56") (pinfunction "PD9_56") (pintype "bidirectional"))
      (node (ref "R72") (pin "1") (pinfunction "1_1") (pintype "passive"))
    )
    (net (code "26") (name "/G6") (class "Default")
      (node (ref "DD1") (pin "57") (pinfunction "PD10_57") (pintype "bidirectional"))
      (node (ref "R73") (pin "1") (pinfunction "1_1") (pintype "passive"))
    )
    (net (code "27") (name "/G7") (class "Default")
      (node (ref "DD1") (pin "58") (pinfunction "PD11_58") (pintype "bidirectional"))
      (node (ref "R74") (pin "1") (pinfunction "1_1") (pintype "passive"))
    )
    (net (code "28") (name "/I2C-SCL{slash}TX") (class "Default")
      (node (ref "DD1") (pin "47") (pinfunction "PB10_47") (pintype "bidirectional"))
      (node (ref "R21") (pin "1") (pinfunction "1_1") (pintype "passive"))
      (node (ref "X6") (pin "2") (pinfunction "2_2") (pintype "passive"))
    )
    (net (code "29") (name "/I2C-SDA{slash}RX") (class "Default")
      (node (ref "DD1") (pin "48") (pinfunction "PB11_48") (pintype "bidirectional"))
      (node (ref "R20") (pin "1") (pinfunction "1_1") (pintype "passive"))
      (node (ref "X6") (pin "3") (pinfunction "3_3") (pintype "passive"))
    )
    (net (code "30") (name "/MDDIR1") (class "Default")
      (node (ref "DD1") (pin "38") (pinfunction "PE7_38") (pintype "bidirectional"))
      (node (ref "X16") (pin "6") (pinfunction "DIR1_6") (pintype "passive"))
    )
    (net (code "31") (name "/MDDIR2") (class "Default")
      (node (ref "DD1") (pin "43") (pinfunction "PE12_43") (pintype "bidirectional"))
      (node (ref "X16") (pin "5") (pinfunction "DIR2_5") (pintype "passive"))
    )
    (net (code "32") (name "/MDPWM1") (class "Default")
      (node (ref "DD1") (pin "44") (pinfunction "PE13_44") (pintype "bidirectional"))
      (node (ref "X16") (pin "2") (pinfunction "PWM1_2") (pintype "passive"))
    )
    (net (code "33") (name "/MDPWM2") (class "Default")
      (node (ref "DD1") (pin "45") (pinfunction "PE14_45") (pintype "bidirectional"))
      (node (ref "X16") (pin "1") (pinfunction "PWM2_1") (pintype "passive"))
    )
    (net (code "34") (name "/RBGP0") (class "Default")
      (node (ref "DD1") (pin "77") (pinfunction "PA15_77") (pintype "bidirectional"))
      (node (ref "DD1") (pin "83") (pinfunction "PD2_83") (pintype "bidirectional"))
      (node (ref "X11") (pin "9") (pinfunction "GP0_9") (pintype "passive"))
    )
    (net (code "35") (name "/RBGP1") (class "Default")
      (node (ref "DD1") (pin "81") (pinfunction "PD0_81") (pintype "bidirectional"))
      (node (ref "X11") (pin "8") (pinfunction "GP1_8") (pintype "passive"))
    )
    (net (code "36") (name "/RBGP2") (class "Default")
      (node (ref "DD1") (pin "82") (pinfunction "PD1_82") (pintype "bidirectional"))
      (node (ref "X11") (pin "7") (pinfunction "GP2_7") (pintype "passive"))
    )
    (net (code "37") (name "/RBMISO") (class "Default")
      (node (ref "DD1") (pin "90") (pinfunction "PB4_90") (pintype "bidirectional"))
      (node (ref "X11") (pin "5") (pinfunction "MISO_5") (pintype "passive"))
    )
    (net (code "38") (name "/RBMOSI") (class "Default")
      (node (ref "DD1") (pin "91") (pinfunction "PB5_91") (pintype "bidirectional"))
      (node (ref "X11") (pin "4") (pinfunction "MOSI_4") (pintype "passive"))
    )
    (net (code "39") (name "/RBRXD") (class "Default")
      (node (ref "R46") (pin "2") (pinfunction "2_2") (pintype "passive"))
      (node (ref "X11") (pin "13") (pinfunction "RXD_13") (pintype "passive"))
    )
    (net (code "40") (name "/RBSCK") (class "Default")
      (node (ref "DD1") (pin "89") (pinfunction "PB3_89") (pintype "bidirectional"))
      (node (ref "X11") (pin "6") (pinfunction "SCK_6") (pintype "passive"))
    )
    (net (code "41") (name "/RBSCL") (class "Default")
      (node (ref "DD1") (pin "92") (pinfunction "PB6_92") (pintype "bidirectional"))
      (node (ref "R3") (pin "2") (pinfunction "2_2") (pintype "passive"))
      (node (ref "X11") (pin "11") (pinfunction "SCL_11") (pintype "passive"))
    )
    (net (code "42") (name "/RBSDA") (class "Default")
      (node (ref "DD1") (pin "93") (pinfunction "PB7_93") (pintype "bidirectional"))
      (node (ref "R2") (pin "2") (pinfunction "2_2") (pintype "passive"))
      (node (ref "X11") (pin "10") (pinfunction "SDA_10") (pintype "passive"))
    )
    (net (code "43") (name "/RBTXD") (class "Default")
      (node (ref "R45") (pin "2") (pinfunction "2_2") (pintype "passive"))
      (node (ref "X11") (pin "12") (pinfunction "TXD_12") (pintype "passive"))
    )
    (net (code "44") (name "/S00") (class "Default")
      (node (ref "DD1") (pin "5") (pinfunction "PE6_5") (pintype "bidirectional"))
      (node (ref "R47") (pin "1") (pinfunction "1_1") (pintype "passive"))
    )
    (net (code "45") (name "/S00C") (class "Default")
      (node (ref "R25") (pin "2") (pinfunction "2_2") (pintype "passive"))
      (node (ref "R47") (pin "2") (pinfunction "2_2") (pintype "passive"))
      (node (ref "X12") (pin "1") (pinfunction "1_1") (pintype "passive"))
    )
    (net (code "46") (name "/S01") (class "Default")
      (node (ref "DD1") (pin "4") (pinfunction "PE5_4") (pintype "bidirectional"))
      (node (ref "R48") (pin "1") (pinfunction "1_1") (pintype "passive"))
    )
    (net (code "47") (name "/S01C") (class "Default")
      (node (ref "R26") (pin "2") (pinfunction "2_2") (pintype "passive"))
      (node (ref "R48") (pin "2") (pinfunction "2_2") (pintype "passive"))
      (node (ref "X12") (pin "2") (pinfunction "2_2") (pintype "passive"))
    )
    (net (code "48") (name "/S02") (class "Default")
      (node (ref "DD1") (pin "3") (pinfunction "PE4_3") (pintype "bidirectional"))
      (node (ref "R49") (pin "1") (pinfunction "1_1") (pintype "passive"))
    )
    (net (code "49") (name "/S02C") (class "Default")
      (node (ref "R27") (pin "2") (pinfunction "2_2") (pintype "passive"))
      (node (ref "R49") (pin "2") (pinfunction "2_2") (pintype "passive"))
      (node (ref "X12") (pin "3") (pinfunction "3_3") (pintype "passive"))
    )
    (net (code "50") (name "/S03") (class "Default")
      (node (ref "DD1") (pin "2") (pinfunction "PE3_2") (pintype "bidirectional"))
      (node (ref "R50") (pin "1") (pinfunction "1_1") (pintype "passive"))
    )
    (net (code "51") (name "/S03C") (class "Default")
      (node (ref "R28") (pin "2") (pinfunction "2_2") (pintype "passive"))
      (node (ref "R50") (pin "2") (pinfunction "2_2") (pintype "passive"))
      (node (ref "X12") (pin "4") (pinfunction "4_4") (pintype "passive"))
    )
    (net (code "52") (name "/S04") (class "Default")
      (node (ref "DD1") (pin "1") (pinfunction "PE2_1") (pintype "bidirectional"))
      (node (ref "R51") (pin "1") (pinfunction "1_1") (pintype "passive"))
    )
    (net (code "53") (name "/S04C") (class "Default")
      (node (ref "R29") (pin "2") (pinfunction "2_2") (pintype "passive"))
      (node (ref "R51") (pin "2") (pinfunction "2_2") (pintype "passive"))
      (node (ref "X12") (pin "5") (pinfunction "5_5") (pintype "passive"))
    )
    (net (code "54") (name "/S05") (class "Default")
      (node (ref "DD1") (pin "98") (pinfunction "PE1_98") (pintype "bidirectional"))
      (node (ref "R52") (pin "1") (pinfunction "1_1") (pintype "passive"))
    )
    (net (code "55") (name "/S05C") (class "Default")
      (node (ref "R30") (pin "2") (pinfunction "2_2") (pintype "passive"))
      (node (ref "R52") (pin "2") (pinfunction "2_2") (pintype "passive"))
      (node (ref "X12") (pin "6") (pinfunction "6_6") (pintype "passive"))
    )
    (net (code "56") (name "/S06") (class "Default")
      (node (ref "DD1") (pin "97") (pinfunction "PE0_97") (pintype "bidirectional"))
      (node (ref "R53") (pin "1") (pinfunction "1_1") (pintype "passive"))
    )
    (net (code "57") (name "/S06C") (class "Default")
      (node (ref "R31") (pin "2") (pinfunction "2_2") (pintype "passive"))
      (node (ref "R53") (pin "2") (pinfunction "2_2") (pintype "passive"))
      (node (ref "X12") (pin "7") (pinfunction "7_7") (pintype "passive"))
    )
    (net (code "58") (name "/S07") (class "Default")
      (node (ref "DD1") (pin "88") (pinfunction "PD7_88") (pintype "bidirectional"))
      (node (ref "R54") (pin "1") (pinfunction "1_1") (pintype "passive"))
    )
    (net (code "59") (name "/S07C") (class "Default")
      (node (ref "R32") (pin "2") (pinfunction "2_2") (pintype "passive"))
      (node (ref "R54") (pin "2") (pinfunction "2_2") (pintype "passive"))
      (node (ref "X12") (pin "8") (pinfunction "8_8") (pintype "passive"))
    )
    (net (code "60") (name "/S08") (class "Default")
      (node (ref "DD1") (pin "87") (pinfunction "PD6_87") (pintype "bidirectional"))
      (node (ref "R55") (pin "1") (pinfunction "1_1") (pintype "passive"))
    )
    (net (code "61") (name "/S08C") (class "Default")
      (node (ref "R33") (pin "2") (pinfunction "2_2") (pintype "passive"))
      (node (ref "R55") (pin "2") (pinfunction "2_2") (pintype "passive"))
      (node (ref "X12") (pin "9") (pinfunction "9_9") (pintype "passive"))
    )
    (net (code "62") (name "/S09") (class "Default")
      (node (ref "DD1") (pin "86") (pinfunction "PD5_86") (pintype "bidirectional"))
      (node (ref "R56") (pin "1") (pinfunction "1_1") (pintype "passive"))
    )
    (net (code "63") (name "/S09C") (class "Default")
      (node (ref "R34") (pin "2") (pinfunction "2_2") (pintype "passive"))
      (node (ref "R56") (pin "2") (pinfunction "2_2") (pintype "passive"))
      (node (ref "X12") (pin "10") (pinfunction "10_10") (pintype "passive"))
    )
    (net (code "64") (name "/S10") (class "Default")
      (node (ref "DD1") (pin "61") (pinfunction "PD14_61") (pintype "bidirectional"))
      (node (ref "R57") (pin "1") (pinfunction "1_1") (pintype "passive"))
    )
    (net (code "65") (name "/S10C") (class "Default")
      (node (ref "R35") (pin "2") (pinfunction "2_2") (pintype "passive"))
      (node (ref "R57") (pin "2") (pinfunction "2_2") (pintype "passive"))
      (node (ref "X13") (pin "1") (pinfunction "1_1") (pintype "passive"))
    )
    (net (code "66") (name "/S11") (class "Default")
      (node (ref "DD1") (pin "62") (pinfunction "PD15_62") (pintype "bidirectional"))
      (node (ref "R58") (pin "1") (pinfunction "1_1") (pintype "passive"))
    )
    (net (code "67") (name "/S11C") (class "Default")
      (node (ref "R36") (pin "2") (pinfunction "2_2") (pintype "passive"))
      (node (ref "R58") (pin "2") (pinfunction "2_2") (pintype "passive"))
      (node (ref "X13") (pin "2") (pinfunction "2_2") (pintype "passive"))
    )
    (net (code "68") (name "/S12") (class "Default")
      (node (ref "DD1") (pin "63") (pinfunction "PC6_63") (pintype "bidirectional"))
      (node (ref "R59") (pin "1") (pinfunction "1_1") (pintype "passive"))
    )
    (net (code "69") (name "/S12C") (class "Default")
      (node (ref "R37") (pin "2") (pinfunction "2_2") (pintype "passive"))
      (node (ref "R59") (pin "2") (pinfunction "2_2") (pintype "passive"))
      (node (ref "X13") (pin "3") (pinfunction "3_3") (pintype "passive"))
    )
    (net (code "70") (name "/S13") (class "Default")
      (node (ref "DD1") (pin "64") (pinfunction "PC7_64") (pintype "bidirectional"))
      (node (ref "R60") (pin "1") (pinfunction "1_1") (pintype "passive"))
    )
    (net (code "71") (name "/S13C") (class "Default")
      (node (ref "R38") (pin "2") (pinfunction "2_2") (pintype "passive"))
      (node (ref "R60") (pin "2") (pinfunction "2_2") (pintype "passive"))
      (node (ref "X13") (pin "4") (pinfunction "4_4") (pintype "passive"))
    )
    (net (code "72") (name "/S14") (class "Default")
      (node (ref "DD1") (pin "65") (pinfunction "PC8_65") (pintype "bidirectional"))
      (node (ref "R61") (pin "1") (pinfunction "1_1") (pintype "passive"))
    )
    (net (code "73") (name "/S14C") (class "Default")
      (node (ref "R39") (pin "2") (pinfunction "2_2") (pintype "passive"))
      (node (ref "R61") (pin "2") (pinfunction "2_2") (pintype "passive"))
      (node (ref "X13") (pin "5") (pinfunction "5_5") (pintype "passive"))
    )
    (net (code "74") (name "/S15") (class "Default")
      (node (ref "DD1") (pin "66") (pinfunction "PC9_66") (pintype "bidirectional"))
      (node (ref "R62") (pin "1") (pinfunction "1_1") (pintype "passive"))
    )
    (net (code "75") (name "/S15C") (class "Default")
      (node (ref "R40") (pin "2") (pinfunction "2_2") (pintype "passive"))
      (node (ref "R62") (pin "2") (pinfunction "2_2") (pintype "passive"))
      (node (ref "X13") (pin "6") (pinfunction "6_6") (pintype "passive"))
    )
    (net (code "76") (name "/S16") (class "Default")
      (node (ref "DD1") (pin "67") (pinfunction "PA8_67") (pintype "bidirectional"))
      (node (ref "R63") (pin "1") (pinfunction "1_1") (pintype "passive"))
    )
    (net (code "77") (name "/S16C") (class "Default")
      (node (ref "R41") (pin "2") (pinfunction "2_2") (pintype "passive"))
      (node (ref "R63") (pin "2") (pinfunction "2_2") (pintype "passive"))
      (node (ref "X13") (pin "7") (pinfunction "7_7") (pintype "passive"))
    )
    (net (code "78") (name "/S17") (class "Default")
      (node (ref "DD1") (pin "78") (pinfunction "PC10_78") (pintype "bidirectional"))
      (node (ref "R64") (pin "1") (pinfunction "1_1") (pintype "passive"))
    )
    (net (code "79") (name "/S17C") (class "Default")
      (node (ref "R42") (pin "2") (pinfunction "2_2") (pintype "passive"))
      (node (ref "R64") (pin "2") (pinfunction "2_2") (pintype "passive"))
      (node (ref "X13") (pin "8") (pinfunction "8_8") (pintype "passive"))
    )
    (net (code "80") (name "/S18") (class "Default")
      (node (ref "DD1") (pin "79") (pinfunction "PC11_79") (pintype "bidirectional"))
      (node (ref "R65") (pin "1") (pinfunction "1_1") (pintype "passive"))
    )
    (net (code "81") (name "/S18C") (class "Default")
      (node (ref "R43") (pin "2") (pinfunction "2_2") (pintype "passive"))
      (node (ref "R65") (pin "2") (pinfunction "2_2") (pintype "passive"))
      (node (ref "X13") (pin "9") (pinfunction "9_9") (pintype "passive"))
    )
    (net (code "82") (name "/S19") (class "Default")
      (node (ref "DD1") (pin "80") (pinfunction "PC12_80") (pintype "bidirectional"))
      (node (ref "R66") (pin "1") (pinfunction "1_1") (pintype "passive"))
    )
    (net (code "83") (name "/S19C") (class "Default")
      (node (ref "R44") (pin "2") (pinfunction "2_2") (pintype "passive"))
      (node (ref "R66") (pin "2") (pinfunction "2_2") (pintype "passive"))
      (node (ref "X13") (pin "10") (pinfunction "10_10") (pintype "passive"))
    )
    (net (code "84") (name "/SWCLK") (class "Default")
      (node (ref "DD1") (pin "76") (pinfunction "PA14_76") (pintype "bidirectional"))
      (node (ref "X9") (pin "2") (pinfunction "2_2") (pintype "passive"))
    )
    (net (code "85") (name "/SWDIO") (class "Default")
      (node (ref "DD1") (pin "72") (pinfunction "PA13_72") (pintype "bidirectional"))
      (node (ref "X9") (pin "4") (pinfunction "4_4") (pintype "passive"))
    )
    (net (code "86") (name "/U2RX") (class "Default")
      (node (ref "DD1") (pin "69") (pinfunction "PA10_69") (pintype "bidirectional"))
      (node (ref "JP5") (pin "1") (pinfunction "1_1") (pintype "passive"))
    )
    (net (code "87") (name "/U2TX") (class "Default")
      (node (ref "DD1") (pin "68") (pinfunction "PA9_68") (pintype "bidirectional"))
      (node (ref "JP5") (pin "4") (pinfunction "4_4") (pintype "passive"))
    )
    (net (code "88") (name "/USBD+") (class "Default")
      (node (ref "DD1") (pin "71") (pinfunction "PA12_71") (pintype "bidirectional"))
      (node (ref "R23") (pin "1") (pinfunction "1_1") (pintype "passive"))
      (node (ref "X5") (pin "D+") (pinfunction "D+_D+") (pintype "bidirectional"))
    )
    (net (code "89") (name "/USBD-") (class "Default")
      (node (ref "DD1") (pin "70") (pinfunction "PA11_70") (pintype "bidirectional"))
      (node (ref "X5") (pin "D-") (pinfunction "D-_D-") (pintype "bidirectional"))
    )
    (net (code "90") (name "/VREF") (class "Default")
      (node (ref "DD2") (pin "5") (pinfunction "VREF_5") (pintype "power_in"))
    )
    (net (code "91") (name "/~{NRST}") (class "Default")
      (node (ref "C12") (pin "1") (pinfunction "1_1") (pintype "passive"))
      (node (ref "DD1") (pin "14") (pinfunction "~{NRST}_14") (pintype "input"))
      (node (ref "SV1") (pin "3") (pinfunction "3_3") (pintype "passive"))
    )
    (net (code "92") (name "GND") (class "Default")
      (node (ref "C1") (pin "-") (pinfunction "-_-") (pintype "passive"))
      (node (ref "C10") (pin "2") (pinfunction "2_2") (pintype "passive"))
      (node (ref "C11") (pin "2") (pinfunction "2_2") (pintype "passive"))
      (node (ref "C12") (pin "2") (pinfunction "2_2") (pintype "passive"))
      (node (ref "C13") (pin "2") (pinfunction "2_2") (pintype "passive"))
      (node (ref "C14") (pin "2") (pinfunction "2_2") (pintype "passive"))
      (node (ref "C2") (pin "-") (pinfunction "-_-") (pintype "passive"))
      (node (ref "C3") (pin "-") (pinfunction "-_-") (pintype "passive"))
      (node (ref "C4") (pin "-") (pinfunction "-_-") (pintype "passive"))
      (node (ref "C5") (pin "1") (pinfunction "1_1") (pintype "passive"))
      (node (ref "C6") (pin "1") (pinfunction "1_1") (pintype "passive"))
      (node (ref "C7") (pin "2") (pinfunction "2_2") (pintype "passive"))
      (node (ref "C8") (pin "2") (pinfunction "2_2") (pintype "passive"))
      (node (ref "C9") (pin "2") (pinfunction "2_2") (pintype "passive"))
      (node (ref "DA1") (pin "1") (pinfunction "GND_1") (pintype "input"))
      (node (ref "DA2") (pin "1") (pinfunction "GND_1") (pintype "input"))
      (node (ref "DD1") (pin "10") (pinfunction "VSS_5_10") (pintype "passive"))
      (node (ref "DD1") (pin "19") (pinfunction "VSSA_19") (pintype "bidirectional"))
      (node (ref "DD1") (pin "20") (pinfunction "VREF-_20") (pintype "bidirectional"))
      (node (ref "DD1") (pin "27") (pinfunction "VSS_4_27") (pintype "passive"))
      (node (ref "DD1") (pin "49") (pinfunction "VSS_1_49") (pintype "passive"))
      (node (ref "DD1") (pin "74") (pinfunction "VSS_2_74") (pintype "passive"))
      (node (ref "DD1") (pin "99") (pinfunction "VSS_3_99") (pintype "passive"))
      (node (ref "DD2") (pin "2") (pinfunction "VSS_2") (pintype "power_in"))
      (node (ref "HL2") (pin "C") (pinfunction "C_C") (pintype "passive"))
      (node (ref "R1") (pin "1") (pinfunction "1_1") (pintype "passive"))
      (node (ref "R11") (pin "1") (pinfunction "1_1") (pintype "passive"))
      (node (ref "R12") (pin "2") (pinfunction "2_2") (pintype "passive"))
      (node (ref "R13") (pin "2") (pinfunction "2_2") (pintype "passive"))
      (node (ref "R14") (pin "1") (pinfunction "1_1") (pintype "passive"))
      (node (ref "R16") (pin "2") (pinfunction "2_2") (pintype "passive"))
      (node (ref "R19") (pin "1") (pinfunction "1_1") (pintype "passive"))
      (node (ref "R22") (pin "2") (pinfunction "2_2") (pintype "passive"))
      (node (ref "R24") (pin "1") (pinfunction "1_1") (pintype "passive"))
      (node (ref "R4") (pin "1") (pinfunction "1_1") (pintype "passive"))
      (node (ref "R5") (pin "2") (pinfunction "2_2") (pintype "passive"))
      (node (ref "R7") (pin "1") (pinfunction "1_1") (pintype "passive"))
      (node (ref "SV1") (pin "1") (pinfunction "1_1") (pintype "passive"))
      (node (ref "SV1") (pin "2") (pinfunction "2_2") (pintype "passive"))
      (node (ref "VT1") (pin "2") (pinfunction "S_2") (pintype "passive"))
      (node (ref "VT2") (pin "1") (pinfunction "S_1") (pintype "passive"))
      (node (ref "VT3") (pin "1") (pinfunction "S_1") (pintype "passive"))
      (node (ref "VT4") (pin "2") (pinfunction "S_2") (pintype "passive"))
      (node (ref "VT5") (pin "2") (pinfunction "S_2") (pintype "passive"))
      (node (ref "VT6") (pin "1") (pinfunction "S_1") (pintype "passive"))
      (node (ref "VT7") (pin "1") (pinfunction "S_1") (pintype "passive"))
      (node (ref "VT8") (pin "2") (pinfunction "S_2") (pintype "passive"))
      (node (ref "X1") (pin "2") (pinfunction "KL_2") (pintype "passive"))
      (node (ref "X10") (pin "1") (pinfunction "1_1") (pintype "passive"))
      (node (ref "X10") (pin "4") (pinfunction "4_4") (pintype "passive"))
      (node (ref "X11") (pin "1") (pinfunction "GND_1") (pintype "passive"))
      (node (ref "X16") (pin "10") (pinfunction "GND1_10") (pintype "passive"))
      (node (ref "X16") (pin "12") (pinfunction "GND2_12") (pintype "passive"))
      (node (ref "X2") (pin "1") (pinfunction "1_1") (pintype "passive"))
      (node (ref "X2") (pin "2") (pinfunction "2_2") (pintype "passive"))
      (node (ref "X21") (pin "1") (pinfunction "1_1") (pintype "passive"))
      (node (ref "X21") (pin "10") (pinfunction "10_10") (pintype "passive"))
      (node (ref "X21") (pin "2") (pinfunction "2_2") (pintype "passive"))
      (node (ref "X21") (pin "3") (pinfunction "3_3") (pintype "passive"))
      (node (ref "X21") (pin "4") (pinfunction "4_4") (pintype "passive"))
      (node (ref "X21") (pin "5") (pinfunction "5_5") (pintype "passive"))
      (node (ref "X21") (pin "6") (pinfunction "6_6") (pintype "passive"))
      (node (ref "X21") (pin "7") (pinfunction "7_7") (pintype "passive"))
      (node (ref "X21") (pin "8") (pinfunction "8_8") (pintype "passive"))
      (node (ref "X21") (pin "9") (pinfunction "9_9") (pintype "passive"))
      (node (ref "X22") (pin "1") (pinfunction "1_1") (pintype "passive"))
      (node (ref "X22") (pin "10") (pinfunction "10_10") (pintype "passive"))
      (node (ref "X22") (pin "2") (pinfunction "2_2") (pintype "passive"))
      (node (ref "X22") (pin "3") (pinfunction "3_3") (pintype "passive"))
      (node (ref "X22") (pin "4") (pinfunction "4_4") (pintype "passive"))
      (node (ref "X22") (pin "5") (pinfunction "5_5") (pintype "passive"))
      (node (ref "X22") (pin "6") (pinfunction "6_6") (pintype "passive"))
      (node (ref "X22") (pin "7") (pinfunction "7_7") (pintype "passive"))
      (node (ref "X22") (pin "8") (pinfunction "8_8") (pintype "passive"))
      (node (ref "X22") (pin "9") (pinfunction "9_9") (pintype "passive"))
      (node (ref "X23") (pin "1") (pinfunction "1_1") (pintype "passive"))
      (node (ref "X23") (pin "2") (pinfunction "2_2") (pintype "passive"))
      (node (ref "X23") (pin "3") (pinfunction "3_3") (pintype "passive"))
      (node (ref "X23") (pin "4") (pinfunction "4_4") (pintype "passive"))
      (node (ref "X23") (pin "5") (pinfunction "5_5") (pintype "passive"))
      (node (ref "X23") (pin "6") (pinfunction "6_6") (pintype "passive"))
      (node (ref "X23") (pin "7") (pinfunction "7_7") (pintype "passive"))
      (node (ref "X23") (pin "8") (pinfunction "8_8") (pintype "passive"))
      (node (ref "X24") (pin "1") (pinfunction "1_1") (pintype "passive"))
      (node (ref "X24") (pin "2") (pinfunction "2_2") (pintype "passive"))
      (node (ref "X24") (pin "3") (pinfunction "3_3") (pintype "passive"))
      (node (ref "X24") (pin "4") (pinfunction "4_4") (pintype "passive"))
      (node (ref "X24") (pin "5") (pinfunction "5_5") (pintype "passive"))
      (node (ref "X24") (pin "6") (pinfunction "6_6") (pintype "passive"))
      (node (ref "X24") (pin "7") (pinfunction "7_7") (pintype "passive"))
      (node (ref "X24") (pin "8") (pinfunction "8_8") (pintype "passive"))
      (node (ref "X25") (pin "2") (pinfunction "KL_2") (pintype "passive"))
      (node (ref "X26") (pin "2") (pinfunction "KL_2") (pintype "passive"))
      (node (ref "X5") (pin "GND") (pinfunction "GND_GND") (pintype "bidirectional"))
      (node (ref "X6") (pin "1") (pinfunction "1_1") (pintype "passive"))
      (node (ref "X7") (pin "4") (pinfunction "4_4") (pintype "passive"))
      (node (ref "X8") (pin "4") (pinfunction "4_4") (pintype "passive"))
      (node (ref "X9") (pin "3") (pinfunction "3_3") (pintype "passive"))
    )
    (net (code "93") (name "M0DIRN") (class "Default")
      (node (ref "DD1") (pin "34") (pinfunction "PC5_34") (pintype "bidirectional"))
      (node (ref "R12") (pin "1") (pinfunction "1_1") (pintype "passive"))
      (node (ref "VT4") (pin "1") (pinfunction "G_1") (pintype "passive"))
    )
    (net (code "94") (name "M0DIRP") (class "Default")
      (node (ref "DD1") (pin "33") (pinfunction "PC4_33") (pintype "bidirectional"))
      (node (ref "R5") (pin "1") (pinfunction "1_1") (pintype "passive"))
      (node (ref "VT1") (pin "1") (pinfunction "G_1") (pintype "passive"))
    )
    (net (code "95") (name "M0PWMN") (class "Default")
      (node (ref "DD1") (pin "39") (pinfunction "PE8_39") (pintype "bidirectional"))
      (node (ref "R11") (pin "2") (pinfunction "2_2") (pintype "passive"))
      (node (ref "VT3") (pin "2") (pinfunction "G_2") (pintype "passive"))
    )
    (net (code "96") (name "M0PWMP") (class "Default")
      (node (ref "DD1") (pin "40") (pinfunction "PE9_40") (pintype "bidirectional"))
      (node (ref "R7") (pin "2") (pinfunction "2_2") (pintype "passive"))
      (node (ref "VT2") (pin "2") (pinfunction "G_2") (pintype "passive"))
    )
    (net (code "97") (name "M1DIRN") (class "Default")
      (node (ref "DD1") (pin "36") (pinfunction "PB1_36") (pintype "bidirectional"))
      (node (ref "R22") (pin "1") (pinfunction "1_1") (pintype "passive"))
      (node (ref "VT8") (pin "1") (pinfunction "G_1") (pintype "passive"))
    )
    (net (code "98") (name "M1DIRP") (class "Default")
      (node (ref "DD1") (pin "35") (pinfunction "PB0_35") (pintype "bidirectional"))
      (node (ref "R13") (pin "1") (pinfunction "1_1") (pintype "passive"))
      (node (ref "VT5") (pin "1") (pinfunction "G_1") (pintype "passive"))
    )
    (net (code "99") (name "M1PWMN") (class "Default")
      (node (ref "DD1") (pin "41") (pinfunction "PE10_41") (pintype "bidirectional"))
      (node (ref "R19") (pin "2") (pinfunction "2_2") (pintype "passive"))
      (node (ref "VT7") (pin "2") (pinfunction "G_2") (pintype "passive"))
    )
    (net (code "100") (name "M1PWMP") (class "Default")
      (node (ref "DD1") (pin "42") (pinfunction "PE11_42") (pintype "bidirectional"))
      (node (ref "R14") (pin "2") (pinfunction "2_2") (pintype "passive"))
      (node (ref "VT6") (pin "2") (pinfunction "G_2") (pintype "passive"))
    )
    (net (code "101") (name "Net-(DA1-OUT)") (class "Default")
      (node (ref "C14") (pin "1") (pinfunction "1_1") (pintype "passive"))
      (node (ref "C3") (pin "+") (pinfunction "+_+") (pintype "passive"))
      (node (ref "DA1") (pin "2") (pinfunction "OUT_2") (pintype "passive"))
      (node (ref "JP3") (pin "1") (pinfunction "1_1") (pintype "passive"))
    )
    (net (code "102") (name "Net-(DA2-OUT)") (class "Default")
      (node (ref "C13") (pin "1") (pinfunction "1_1") (pintype "passive"))
      (node (ref "C4") (pin "+") (pinfunction "+_+") (pintype "passive"))
      (node (ref "DA2") (pin "2") (pinfunction "OUT_2") (pintype "passive"))
      (node (ref "JP4") (pin "1") (pinfunction "1_1") (pintype "passive"))
    )
    (net (code "103") (name "Net-(DD1-BOOT0)") (class "Default")
      (node (ref "DD1") (pin "94") (pinfunction "BOOT0_94") (pintype "input"))
      (node (ref "R16") (pin "1") (pinfunction "1_1") (pintype "passive"))
      (node (ref "SV2") (pin "1") (pinfunction "1_1") (pintype "passive"))
    )
    (net (code "104") (name "Net-(DD1-OSC_IN)") (class "Default")
      (node (ref "C5") (pin "2") (pinfunction "2_2") (pintype "passive"))
      (node (ref "DD1") (pin "12") (pinfunction "OSC_IN_12") (pintype "input"))
      (node (ref "ZQ1") (pin "2") (pinfunction "2_2") (pintype "passive"))
    )
    (net (code "105") (name "Net-(DD1-OSC_OUT)") (class "Default")
      (node (ref "C6") (pin "2") (pinfunction "2_2") (pintype "passive"))
      (node (ref "DD1") (pin "13") (pinfunction "OSC_OUT_13") (pintype "output"))
      (node (ref "ZQ1") (pin "1") (pinfunction "1_1") (pintype "passive"))
    )
    (net (code "106") (name "Net-(DD2-CANH)") (class "Default")
      (node (ref "DD2") (pin "7") (pinfunction "CANH_7") (pintype "bidirectional"))
      (node (ref "X10") (pin "2") (pinfunction "2_2") (pintype "passive"))
    )
    (net (code "107") (name "Net-(DD2-CANL)") (class "Default")
      (node (ref "DD2") (pin "6") (pinfunction "CANL_6") (pintype "bidirectional"))
      (node (ref "X10") (pin "3") (pinfunction "3_3") (pintype "passive"))
    )
    (net (code "108") (name "Net-(DD2-RS)") (class "Default")
      (node (ref "DD2") (pin "8") (pinfunction "RS_8") (pintype "input"))
      (node (ref "R24") (pin "2") (pinfunction "2_2") (pintype "passive"))
    )
    (net (code "109") (name "Net-(HL1-PadC)") (class "Default")
      (node (ref "HL1") (pin "C") (pinfunction "C_C") (pintype "passive"))
      (node (ref "R1") (pin "2") (pinfunction "2_2") (pintype "passive"))
    )
    (net (code "110") (name "Net-(HL2-PadA)") (class "Default")
      (node (ref "HL2") (pin "A") (pinfunction "A_A") (pintype "passive"))
      (node (ref "R6") (pin "1") (pinfunction "1_1") (pintype "passive"))
    )
    (net (code "111") (name "Net-(HL3A-A)") (class "Default")
      (node (ref "HL3") (pin "1") (pinfunction "C_1") (pintype "passive"))
      (node (ref "HL3") (pin "4") (pinfunction "A_4") (pintype "passive"))
      (node (ref "R9") (pin "2") (pinfunction "2_2") (pintype "passive"))
    )
    (net (code "112") (name "Net-(HL3A-C)") (class "Default")
      (node (ref "HL3") (pin "2") (pinfunction "A_2") (pintype "passive"))
      (node (ref "HL3") (pin "3") (pinfunction "C_3") (pintype "passive"))
      (node (ref "VT3") (pin "5") (pinfunction "D_5") (pintype "passive"))
      (node (ref "VT3") (pin "6") (pinfunction "D2_6") (pintype "passive"))
      (node (ref "VT3") (pin "7") (pinfunction "D_7") (pintype "passive"))
      (node (ref "VT3") (pin "8") (pinfunction "D2_8") (pintype "passive"))
      (node (ref "X3") (pin "2") (pinfunction "KL_2") (pintype "passive"))
    )
    (net (code "113") (name "Net-(HL4A-A)") (class "Default")
      (node (ref "HL4") (pin "1") (pinfunction "C_1") (pintype "passive"))
      (node (ref "HL4") (pin "4") (pinfunction "A_4") (pintype "passive"))
      (node (ref "R17") (pin "2") (pinfunction "2_2") (pintype "passive"))
    )
    (net (code "114") (name "Net-(HL4A-C)") (class "Default")
      (node (ref "HL4") (pin "2") (pinfunction "A_2") (pintype "passive"))
      (node (ref "HL4") (pin "3") (pinfunction "C_3") (pintype "passive"))
      (node (ref "VT7") (pin "5") (pinfunction "D_5") (pintype "passive"))
      (node (ref "VT7") (pin "6") (pinfunction "D2_6") (pintype "passive"))
      (node (ref "VT7") (pin "7") (pinfunction "D_7") (pintype "passive"))
      (node (ref "VT7") (pin "8") (pinfunction "D2_8") (pintype "passive"))
      (node (ref "X4") (pin "2") (pinfunction "KL_2") (pintype "passive"))
    )
    (net (code "115") (name "Net-(JP5-Pad2)") (class "Default")
      (node (ref "JP5") (pin "2") (pinfunction "2_2") (pintype "passive"))
      (node (ref "R45") (pin "1") (pinfunction "1_1") (pintype "passive"))
    )
    (net (code "116") (name "Net-(JP5-Pad3)") (class "Default")
      (node (ref "JP5") (pin "3") (pinfunction "3_3") (pintype "passive"))
      (node (ref "R46") (pin "1") (pinfunction "1_1") (pintype "passive"))
    )
    (net (code "117") (name "Net-(JP6-Pad2)") (class "Default")
      (node (ref "JP6") (pin "2") (pinfunction "2_2") (pintype "passive"))
      (node (ref "X19") (pin "1") (pinfunction "1_1") (pintype "passive"))
      (node (ref "X19") (pin "2") (pinfunction "2_2") (pintype "passive"))
      (node (ref "X19") (pin "3") (pinfunction "3_3") (pintype "passive"))
      (node (ref "X19") (pin "4") (pinfunction "4_4") (pintype "passive"))
      (node (ref "X19") (pin "5") (pinfunction "5_5") (pintype "passive"))
      (node (ref "X19") (pin "6") (pinfunction "6_6") (pintype "passive"))
      (node (ref "X19") (pin "7") (pinfunction "7_7") (pintype "passive"))
      (node (ref "X19") (pin "8") (pinfunction "8_8") (pintype "passive"))
    )
    (net (code "118") (name "Net-(JP7-Pad2)") (class "Default")
      (node (ref "JP7") (pin "2") (pinfunction "2_2") (pintype "passive"))
      (node (ref "X20") (pin "1") (pinfunction "1_1") (pintype "passive"))
      (node (ref "X20") (pin "2") (pinfunction "2_2") (pintype "passive"))
      (node (ref "X20") (pin "3") (pinfunction "3_3") (pintype "passive"))
      (node (ref "X20") (pin "4") (pinfunction "4_4") (pintype "passive"))
      (node (ref "X20") (pin "5") (pinfunction "5_5") (pintype "passive"))
      (node (ref "X20") (pin "6") (pinfunction "6_6") (pintype "passive"))
      (node (ref "X20") (pin "7") (pinfunction "7_7") (pintype "passive"))
      (node (ref "X20") (pin "8") (pinfunction "8_8") (pintype "passive"))
    )
    (net (code "119") (name "Net-(R67-Pad2)") (class "Default")
      (node (ref "R67") (pin "2") (pinfunction "2_2") (pintype "passive"))
      (node (ref "X14") (pin "1") (pinfunction "1_1") (pintype "passive"))
    )
    (net (code "120") (name "Net-(R68-Pad2)") (class "Default")
      (node (ref "R68") (pin "2") (pinfunction "2_2") (pintype "passive"))
      (node (ref "X14") (pin "2") (pinfunction "2_2") (pintype "passive"))
    )
    (net (code "121") (name "Net-(R69-Pad2)") (class "Default")
      (node (ref "R69") (pin "2") (pinfunction "2_2") (pintype "passive"))
      (node (ref "X14") (pin "3") (pinfunction "3_3") (pintype "passive"))
    )
    (net (code "122") (name "Net-(R70-Pad2)") (class "Default")
      (node (ref "R70") (pin "2") (pinfunction "2_2") (pintype "passive"))
      (node (ref "X14") (pin "4") (pinfunction "4_4") (pintype "passive"))
    )
    (net (code "123") (name "Net-(R71-Pad2)") (class "Default")
      (node (ref "R71") (pin "2") (pinfunction "2_2") (pintype "passive"))
      (node (ref "X14") (pin "5") (pinfunction "5_5") (pintype "passive"))
    )
    (net (code "124") (name "Net-(R72-Pad2)") (class "Default")
      (node (ref "R72") (pin "2") (pinfunction "2_2") (pintype "passive"))
      (node (ref "X14") (pin "6") (pinfunction "6_6") (pintype "passive"))
    )
    (net (code "125") (name "Net-(R73-Pad2)") (class "Default")
      (node (ref "R73") (pin "2") (pinfunction "2_2") (pintype "passive"))
      (node (ref "X14") (pin "7") (pinfunction "7_7") (pintype "passive"))
    )
    (net (code "126") (name "Net-(R74-Pad2)") (class "Default")
      (node (ref "R74") (pin "2") (pinfunction "2_2") (pintype "passive"))
      (node (ref "X14") (pin "8") (pinfunction "8_8") (pintype "passive"))
    )
    (net (code "127") (name "Net-(R75-Pad2)") (class "Default")
      (node (ref "R75") (pin "2") (pinfunction "2_2") (pintype "passive"))
      (node (ref "X15") (pin "1") (pinfunction "1_1") (pintype "passive"))
    )
    (net (code "128") (name "Net-(R76-Pad2)") (class "Default")
      (node (ref "R76") (pin "2") (pinfunction "2_2") (pintype "passive"))
      (node (ref "X15") (pin "2") (pinfunction "2_2") (pintype "passive"))
    )
    (net (code "129") (name "Net-(R77-Pad2)") (class "Default")
      (node (ref "R77") (pin "2") (pinfunction "2_2") (pintype "passive"))
      (node (ref "X15") (pin "3") (pinfunction "3_3") (pintype "passive"))
    )
    (net (code "130") (name "Net-(R78-Pad2)") (class "Default")
      (node (ref "R78") (pin "2") (pinfunction "2_2") (pintype "passive"))
      (node (ref "X15") (pin "4") (pinfunction "4_4") (pintype "passive"))
    )
    (net (code "131") (name "Net-(R79-Pad2)") (class "Default")
      (node (ref "R79") (pin "2") (pinfunction "2_2") (pintype "passive"))
      (node (ref "X15") (pin "5") (pinfunction "5_5") (pintype "passive"))
    )
    (net (code "132") (name "Net-(R80-Pad2)") (class "Default")
      (node (ref "R80") (pin "2") (pinfunction "2_2") (pintype "passive"))
      (node (ref "X15") (pin "6") (pinfunction "6_6") (pintype "passive"))
    )
    (net (code "133") (name "Net-(R81-Pad2)") (class "Default")
      (node (ref "R81") (pin "2") (pinfunction "2_2") (pintype "passive"))
      (node (ref "X15") (pin "7") (pinfunction "7_7") (pintype "passive"))
    )
    (net (code "134") (name "Net-(R82-Pad2)") (class "Default")
      (node (ref "R82") (pin "2") (pinfunction "2_2") (pintype "passive"))
      (node (ref "X15") (pin "8") (pinfunction "8_8") (pintype "passive"))
    )
    (net (code "135") (name "Net-(VT1-D)") (class "Default")
      (node (ref "R8") (pin "1") (pinfunction "1_1") (pintype "passive"))
      (node (ref "VT1") (pin "3") (pinfunction "D_3") (pintype "passive"))
      (node (ref "VT2") (pin "4") (pinfunction "G_4") (pintype "passive"))
    )
    (net (code "136") (name "Net-(VT2A-D)") (class "Default")
      (node (ref "R9") (pin "1") (pinfunction "1_1") (pintype "passive"))
      (node (ref "VT2") (pin "5") (pinfunction "D_5") (pintype "passive"))
      (node (ref "VT2") (pin "6") (pinfunction "D2_6") (pintype "passive"))
      (node (ref "VT2") (pin "7") (pinfunction "D_7") (pintype "passive"))
      (node (ref "VT2") (pin "8") (pinfunction "D2_8") (pintype "passive"))
      (node (ref "X3") (pin "1") (pinfunction "KL_1") (pintype "passive"))
    )
    (net (code "137") (name "Net-(VT3B-G)") (class "Default")
      (node (ref "R10") (pin "2") (pinfunction "2_2") (pintype "passive"))
      (node (ref "VT3") (pin "4") (pinfunction "G_4") (pintype "passive"))
      (node (ref "VT4") (pin "3") (pinfunction "D_3") (pintype "passive"))
    )
    (net (code "138") (name "Net-(VT5-D)") (class "Default")
      (node (ref "R15") (pin "1") (pinfunction "1_1") (pintype "passive"))
      (node (ref "VT5") (pin "3") (pinfunction "D_3") (pintype "passive"))
      (node (ref "VT6") (pin "4") (pinfunction "G_4") (pintype "passive"))
    )
    (net (code "139") (name "Net-(VT6A-D)") (class "Default")
      (node (ref "R17") (pin "1") (pinfunction "1_1") (pintype "passive"))
      (node (ref "VT6") (pin "5") (pinfunction "D_5") (pintype "passive"))
      (node (ref "VT6") (pin "6") (pinfunction "D2_6") (pintype "passive"))
      (node (ref "VT6") (pin "7") (pinfunction "D_7") (pintype "passive"))
      (node (ref "VT6") (pin "8") (pinfunction "D2_8") (pintype "passive"))
      (node (ref "X4") (pin "1") (pinfunction "KL_1") (pintype "passive"))
    )
    (net (code "140") (name "Net-(VT7B-G)") (class "Default")
      (node (ref "R18") (pin "2") (pinfunction "2_2") (pintype "passive"))
      (node (ref "VT7") (pin "4") (pinfunction "G_4") (pintype "passive"))
      (node (ref "VT8") (pin "3") (pinfunction "D_3") (pintype "passive"))
    )
    (net (code "141") (name "VMD") (class "Default")
      (node (ref "C1") (pin "+") (pinfunction "+_+") (pintype "passive"))
      (node (ref "C2") (pin "+") (pinfunction "+_+") (pintype "passive"))
      (node (ref "R10") (pin "1") (pinfunction "1_1") (pintype "passive"))
      (node (ref "R15") (pin "2") (pinfunction "2_2") (pintype "passive"))
      (node (ref "R18") (pin "1") (pinfunction "1_1") (pintype "passive"))
      (node (ref "R8") (pin "2") (pinfunction "2_2") (pintype "passive"))
      (node (ref "VT2") (pin "3") (pinfunction "S_3") (pintype "passive"))
      (node (ref "VT3") (pin "3") (pinfunction "S_3") (pintype "passive"))
      (node (ref "VT6") (pin "3") (pinfunction "S_3") (pintype "passive"))
      (node (ref "VT7") (pin "3") (pinfunction "S_3") (pintype "passive"))
      (node (ref "X1") (pin "1") (pinfunction "KL_1") (pintype "passive"))
    )
    (net (code "142") (name "VS0") (class "Default")
      (node (ref "JP7") (pin "3") (pinfunction "3_3") (pintype "passive"))
      (node (ref "X17") (pin "1") (pinfunction "1_1") (pintype "passive"))
      (node (ref "X17") (pin "10") (pinfunction "10_10") (pintype "passive"))
      (node (ref "X17") (pin "2") (pinfunction "2_2") (pintype "passive"))
      (node (ref "X17") (pin "3") (pinfunction "3_3") (pintype "passive"))
      (node (ref "X17") (pin "4") (pinfunction "4_4") (pintype "passive"))
      (node (ref "X17") (pin "5") (pinfunction "5_5") (pintype "passive"))
      (node (ref "X17") (pin "6") (pinfunction "6_6") (pintype "passive"))
      (node (ref "X17") (pin "7") (pinfunction "7_7") (pintype "passive"))
      (node (ref "X17") (pin "8") (pinfunction "8_8") (pintype "passive"))
      (node (ref "X17") (pin "9") (pinfunction "9_9") (pintype "passive"))
      (node (ref "X25") (pin "1") (pinfunction "KL_1") (pintype "passive"))
    )
    (net (code "143") (name "VS1") (class "Default")
      (node (ref "DA1") (pin "3") (pinfunction "IN_3") (pintype "input"))
      (node (ref "DA2") (pin "3") (pinfunction "IN_3") (pintype "input"))
      (node (ref "JP6") (pin "3") (pinfunction "3_3") (pintype "passive"))
      (node (ref "X18") (pin "1") (pinfunction "1_1") (pintype "passive"))
      (node (ref "X18") (pin "10") (pinfunction "10_10") (pintype "passive"))
      (node (ref "X18") (pin "2") (pinfunction "2_2") (pintype "passive"))
      (node (ref "X18") (pin "3") (pinfunction "3_3") (pintype "passive"))
      (node (ref "X18") (pin "4") (pinfunction "4_4") (pintype "passive"))
      (node (ref "X18") (pin "5") (pinfunction "5_5") (pintype "passive"))
      (node (ref "X18") (pin "6") (pinfunction "6_6") (pintype "passive"))
      (node (ref "X18") (pin "7") (pinfunction "7_7") (pintype "passive"))
      (node (ref "X18") (pin "8") (pinfunction "8_8") (pintype "passive"))
      (node (ref "X18") (pin "9") (pinfunction "9_9") (pintype "passive"))
      (node (ref "X26") (pin "1") (pinfunction "KL_1") (pintype "passive"))
    )
    (net (code "144") (name "unconnected-(DD1-NC-Pad73)") (class "Default")
      (node (ref "DD1") (pin "73") (pinfunction "NC_73") (pintype "no_connect"))
    )
    (net (code "145") (name "unconnected-(DD1-PC13-TAMPER-RTC-Pad7)") (class "Default")
      (node (ref "DD1") (pin "7") (pinfunction "PC13-TAMPER-RTC_7") (pintype "bidirectional"))
    )
    (net (code "146") (name "unconnected-(DD1-PC14-OSC32_IN-Pad8)") (class "Default")
      (node (ref "DD1") (pin "8") (pinfunction "PC14-OSC32_IN_8") (pintype "bidirectional"))
    )
    (net (code "147") (name "unconnected-(DD1-PC15-OSC32_OUT-Pad9)") (class "Default")
      (node (ref "DD1") (pin "9") (pinfunction "PC15-OSC32_OUT_9") (pintype "bidirectional"))
    )
    (net (code "148") (name "unconnected-(DD1-PD3-Pad84)") (class "Default")
      (node (ref "DD1") (pin "84") (pinfunction "PD3_84") (pintype "bidirectional"))
    )
    (net (code "149") (name "unconnected-(DD1-PD4-Pad85)") (class "Default")
      (node (ref "DD1") (pin "85") (pinfunction "PD4_85") (pintype "bidirectional"))
    )
    (net (code "150") (name "unconnected-(DD1-PE15-Pad46)") (class "Default")
      (node (ref "DD1") (pin "46") (pinfunction "PE15_46") (pintype "bidirectional"))
    )
    (net (code "151") (name "unconnected-(DD1-VBAT-Pad6)") (class "Default")
      (node (ref "DD1") (pin "6") (pinfunction "VBAT_6") (pintype "bidirectional"))
    )
    (net (code "152") (name "unconnected-(SV1-Pad4)") (class "Default")
      (node (ref "SV1") (pin "4") (pinfunction "4_4") (pintype "passive"))
    )
    (net (code "153") (name "unconnected-(SV2-Pad2)") (class "Default")
      (node (ref "SV2") (pin "2") (pinfunction "2_2") (pintype "passive"))
    )
    (net (code "154") (name "unconnected-(SV2-Pad4)") (class "Default")
      (node (ref "SV2") (pin "4") (pinfunction "4_4") (pintype "passive"))
    )
    (net (code "155") (name "unconnected-(X5-PadVBUS)") (class "Default")
      (node (ref "X5") (pin "VBUS") (pinfunction "VBUS_VBUS") (pintype "bidirectional"))
    )
    (net (code "156") (name "unconnected-(X11-RESET-Pad3)") (class "Default")
      (node (ref "X11") (pin "3") (pinfunction "RESET_3") (pintype "passive"))
    )
    (net (code "157") (name "unconnected-(X16-OVLD1-Pad4)") (class "Default")
      (node (ref "X16") (pin "4") (pinfunction "OVLD1_4") (pintype "passive"))
    )
    (net (code "158") (name "unconnected-(X16-OVLD2-Pad3)") (class "Default")
      (node (ref "X16") (pin "3") (pinfunction "OVLD2_3") (pintype "passive"))
    )
    (net (code "159") (name "unconnected-(X16-SENS1-Pad8)") (class "Default")
      (node (ref "X16") (pin "8") (pinfunction "SENS1_8") (pintype "passive"))
    )
    (net (code "160") (name "unconnected-(X16-SENS2-Pad7)") (class "Default")
      (node (ref "X16") (pin "7") (pinfunction "SENS2_7") (pintype "passive"))
    )
    (net (code "161") (name "unconnected-(X16-VSS1-Pad9)") (class "Default")
      (node (ref "X16") (pin "9") (pinfunction "VSS1_9") (pintype "passive"))
    )
    (net (code "162") (name "unconnected-(X16-VSS2-Pad11)") (class "Default")
      (node (ref "X16") (pin "11") (pinfunction "VSS2_11") (pintype "passive"))
    )
  )
)
